# roll_paper_output.net
KiCad netlist of a schematic drawn in Altium Designer
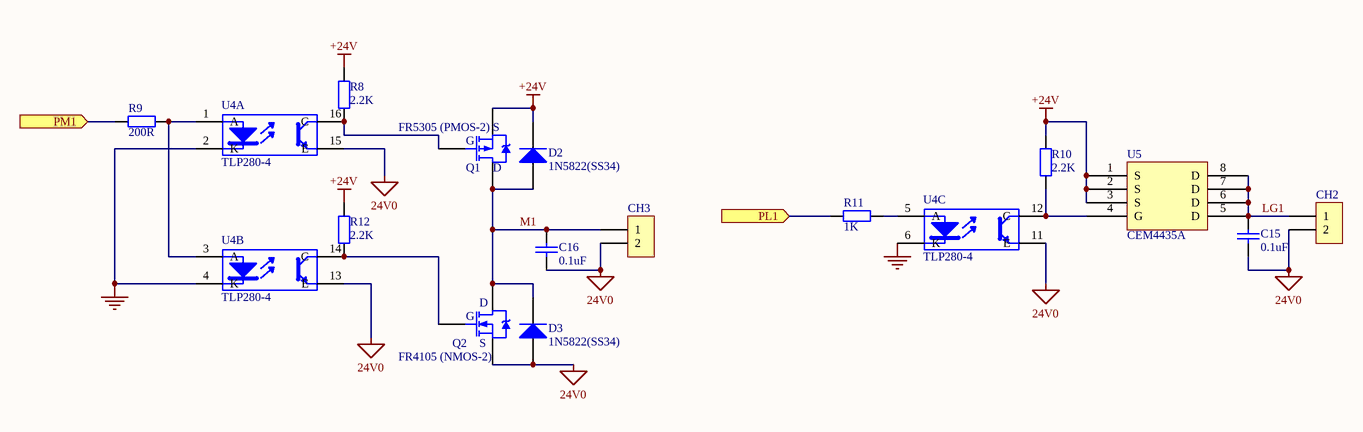
[diagram p0: roll_paper_output.SchDoc]

(export (version "E")
  (design (tool "Eeschema 10.0.6"))
  (components
    (comp (ref "C15")
      (value "0.1uF")
      (footprint "0805")
      (description "Capacitor")
      (fields (field (name "Comment") "Cap") (field (name "PUBLISHER") "Altium Limited"))
      (libsource (lib "Miscellaneous Devices") (part "Cap"))
    )
    (comp (ref "C16")
      (value "0.1uF")
      (footprint "0805")
      (description "Capacitor")
      (fields (field (name "Comment") "Cap") (field (name "PUBLISHER") "Altium Limited"))
      (libsource (lib "Miscellaneous Devices") (part "Cap"))
    )
    (comp (ref "CH2")
      (value "HEADER1X2")
      (footprint "CH3.96-2PIN")
      (libsource (lib "myIntegrated_Library1") (part "HEADER1X2"))
    )
    (comp (ref "CH3")
      (value "HEADER1X2")
      (footprint "CH3.96-2PIN")
      (libsource (lib "myIntegrated_Library1") (part "HEADER1X2"))
    )
    (comp (ref "D2")
      (value "1N5822(SS34)")
      (description "High Conductance Fast Diode")
      (fields (field (name "PUBLISHER") "Altium Limited"))
      (libsource (lib "Miscellaneous Devices") (part "Diode 1N4148"))
    )
    (comp (ref "D3")
      (value "1N5822(SS34)")
      (description "High Conductance Fast Diode")
      (fields (field (name "PUBLISHER") "Altium Limited"))
      (libsource (lib "Miscellaneous Devices") (part "Diode 1N4148"))
    )
    (comp (ref "Q1")
      (value "FR5305 (PMOS-2)")
      (footprint "TO-252")
      (description "P-Channel Power MOSFET")
      (fields (field (name "PUBLISHER") "Altium Limited"))
      (libsource (lib "Miscellaneous Devices") (part "PMOS-2"))
    )
    (comp (ref "Q2")
      (value "FR4105 (NMOS-2)")
      (footprint "TO-252")
      (description "N-Channel Power MOSFET")
      (fields (field (name "PUBLISHER") "Altium Limited"))
      (libsource (lib "Miscellaneous Devices") (part "NMOS-2"))
    )
    (comp (ref "R8")
      (value "2.2K")
      (footprint "0805")
      (description "Resistor")
      (fields (field (name "Comment") "Res2") (field (name "PUBLISHER") "Altium Limited"))
      (libsource (lib "") (part "Res2_1"))
    )
    (comp (ref "R9")
      (value "200R")
      (footprint "0805")
      (description "Resistor")
      (fields (field (name "Comment") "Res2") (field (name "PUBLISHER") "Altium Limited"))
      (libsource (lib "Miscellaneous Devices") (part "Res2"))
    )
    (comp (ref "R10")
      (value "2.2K")
      (footprint "0805")
      (description "Resistor")
      (fields (field (name "Comment") "Res2") (field (name "PUBLISHER") "Altium Limited"))
      (libsource (lib "") (part "Res2_1"))
    )
    (comp (ref "R11")
      (value "1K")
      (footprint "0805")
      (description "Resistor")
      (fields (field (name "Comment") "Res2") (field (name "PUBLISHER") "Altium Limited"))
      (libsource (lib "Miscellaneous Devices") (part "Res2"))
    )
    (comp (ref "R12")
      (value "2.2K")
      (footprint "0805")
      (description "Resistor")
      (fields (field (name "Comment") "Res2") (field (name "PUBLISHER") "Altium Limited"))
      (libsource (lib "") (part "Res2_1"))
    )
    (comp (ref "U4") (value "TLP280-4") (footprint "SO16") (libsource (lib "WH V20") (part "TLP521-4")))
    (comp (ref "U5")
      (value "CEM4435A")
      (footprint "SOP8-OP27")
      (libsource (lib "myIntegrated_Library1") (part "CEM4435A"))
    )
  )
  (nets
    (net (code "1") (name "+24V") (class "Default")
      (node (ref "D2") (pin "2") (pinfunction "K_2") (pintype "passive"))
      (node (ref "Q1") (pin "3") (pinfunction "S_3") (pintype "passive"))
      (node (ref "R10") (pin "2") (pinfunction "2_2") (pintype "passive"))
      (node (ref "R12") (pin "2") (pinfunction "2_2") (pintype "passive"))
      (node (ref "R8") (pin "2") (pinfunction "2_2") (pintype "passive"))
      (node (ref "U5") (pin "1") (pinfunction "S_1") (pintype "passive"))
      (node (ref "U5") (pin "2") (pinfunction "S_2") (pintype "passive"))
      (node (ref "U5") (pin "3") (pinfunction "S_3") (pintype "passive"))
    )
    (net (code "2") (name "/LG1") (class "Default")
      (node (ref "C15") (pin "1") (pinfunction "1_1") (pintype "passive"))
      (node (ref "CH2") (pin "1") (pinfunction "1_1") (pintype "passive"))
      (node (ref "U5") (pin "5") (pinfunction "D_5") (pintype "passive"))
      (node (ref "U5") (pin "6") (pinfunction "D_6") (pintype "passive"))
      (node (ref "U5") (pin "7") (pinfunction "D_7") (pintype "passive"))
      (node (ref "U5") (pin "8") (pinfunction "D_8") (pintype "passive"))
    )
    (net (code "3") (name "/M1") (class "Default")
      (node (ref "C16") (pin "1") (pinfunction "1_1") (pintype "passive"))
      (node (ref "CH3") (pin "1") (pinfunction "1_1") (pintype "passive"))
      (node (ref "D2") (pin "1") (pinfunction "A_1") (pintype "passive"))
      (node (ref "D3") (pin "2") (pinfunction "K_2") (pintype "passive"))
      (node (ref "Q1") (pin "2") (pinfunction "D_2") (pintype "passive"))
      (node (ref "Q2") (pin "2") (pinfunction "D_2") (pintype "passive"))
    )
    (net (code "4") (name "/PL1") (class "Default")
      (node (ref "R11") (pin "1") (pinfunction "1_1") (pintype "passive"))
    )
    (net (code "5") (name "/PM1") (class "Default")
      (node (ref "R9") (pin "1") (pinfunction "1_1") (pintype "passive"))
    )
    (net (code "6") (name "24V0") (class "Default")
      (node (ref "C15") (pin "2") (pinfunction "2_2") (pintype "passive"))
      (node (ref "C16") (pin "2") (pinfunction "2_2") (pintype "passive"))
      (node (ref "CH2") (pin "2") (pinfunction "2_2") (pintype "passive"))
      (node (ref "CH3") (pin "2") (pinfunction "2_2") (pintype "passive"))
      (node (ref "D3") (pin "1") (pinfunction "A_1") (pintype "passive"))
      (node (ref "Q2") (pin "3") (pinfunction "S_3") (pintype "passive"))
      (node (ref "U4") (pin "11") (pinfunction "E_11") (pintype "passive"))
      (node (ref "U4") (pin "13") (pinfunction "E_13") (pintype "passive"))
      (node (ref "U4") (pin "15") (pinfunction "E_15") (pintype "passive"))
    )
    (net (code "7") (name "GND") (class "Default")
      (node (ref "U4") (pin "2") (pinfunction "K_2") (pintype "passive"))
      (node (ref "U4") (pin "4") (pinfunction "K_4") (pintype "passive"))
      (node (ref "U4") (pin "6") (pinfunction "K_6") (pintype "passive"))
    )
    (net (code "8") (name "Net-(Q1-G)") (class "Default")
      (node (ref "Q1") (pin "1") (pinfunction "G_1") (pintype "passive"))
      (node (ref "R8") (pin "1") (pinfunction "1_1") (pintype "passive"))
      (node (ref "U4") (pin "16") (pinfunction "C_16") (pintype "passive"))
    )
    (net (code "9") (name "Net-(Q2-G)") (class "Default")
      (node (ref "Q2") (pin "1") (pinfunction "G_1") (pintype "passive"))
      (node (ref "R12") (pin "1") (pinfunction "1_1") (pintype "passive"))
      (node (ref "U4") (pin "14") (pinfunction "C_14") (pintype "passive"))
    )
    (net (code "10") (name "Net-(U4A-A)") (class "Default")
      (node (ref "R9") (pin "2") (pinfunction "2_2") (pintype "passive"))
      (node (ref "U4") (pin "1") (pinfunction "A_1") (pintype "passive"))
      (node (ref "U4") (pin "3") (pinfunction "A_3") (pintype "passive"))
    )
    (net (code "11") (name "Net-(U4C-A)") (class "Default")
      (node (ref "R11") (pin "2") (pinfunction "2_2") (pintype "passive"))
      (node (ref "U4") (pin "5") (pinfunction "A_5") (pintype "passive"))
    )
    (net (code "12") (name "Net-(U4C-C)") (class "Default")
      (node (ref "R10") (pin "1") (pinfunction "1_1") (pintype "passive"))
      (node (ref "U4") (pin "12") (pinfunction "C_12") (pintype "passive"))
      (node (ref "U5") (pin "4") (pinfunction "G_4") (pintype "passive"))
    )
  )
)
